# shoulder.net
KiCad netlist of a schematic drawn in EAGLE
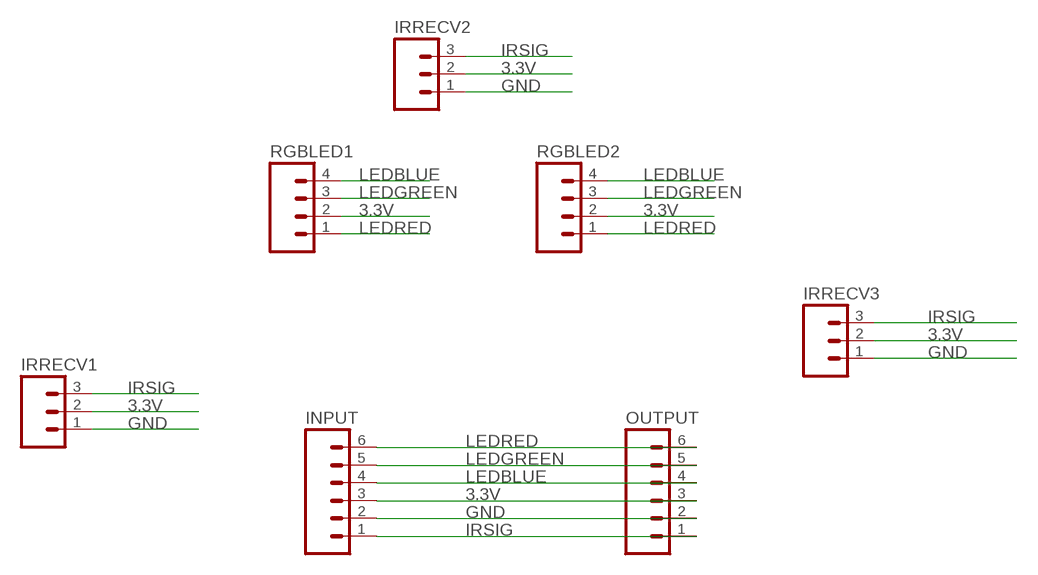
[diagram p0: schematic, sheet 1]

(export (version "E")
  (design (tool "Eeschema 10.0.6"))
  (components
    (comp (ref "INPUT")
      (value "M06SILK_FEMALE_PTH")
      (footprint "eagle-import:1X06")
      (libsource (lib "eagle-import") (part "M06SILK_FEMALE_PTH"))
    )
    (comp (ref "IRRECV1")
      (value "M03PTH")
      (footprint "eagle-import:1X03")
      (libsource (lib "eagle-import") (part "M03PTH"))
    )
    (comp (ref "IRRECV2")
      (value "M03PTH")
      (footprint "eagle-import:1X03")
      (libsource (lib "eagle-import") (part "M03PTH"))
    )
    (comp (ref "IRRECV3")
      (value "M03PTH")
      (footprint "eagle-import:1X03")
      (libsource (lib "eagle-import") (part "M03PTH"))
    )
    (comp (ref "OUTPUT")
      (value "M06SILK_FEMALE_PTH")
      (footprint "eagle-import:1X06")
      (libsource (lib "eagle-import") (part "M06SILK_FEMALE_PTH"))
    )
    (comp (ref "RGBLED1")
      (value "M04PTH")
      (footprint "eagle-import:1X04")
      (libsource (lib "eagle-import") (part "M04PTH"))
    )
    (comp (ref "RGBLED2")
      (value "M04PTH")
      (footprint "eagle-import:1X04")
      (libsource (lib "eagle-import") (part "M04PTH"))
    )
  )
  (nets
    (net (code "1") (name "/3.3V") (class "Default")
      (node (ref "INPUT") (pin "3") (pinfunction "3_3") (pintype "passive"))
      (node (ref "IRRECV1") (pin "2") (pinfunction "2_2") (pintype "passive"))
      (node (ref "IRRECV2") (pin "2") (pinfunction "2_2") (pintype "passive"))
      (node (ref "IRRECV3") (pin "2") (pinfunction "2_2") (pintype "passive"))
      (node (ref "OUTPUT") (pin "3") (pinfunction "3_3") (pintype "passive"))
      (node (ref "RGBLED1") (pin "2") (pinfunction "2_2") (pintype "passive"))
      (node (ref "RGBLED2") (pin "2") (pinfunction "2_2") (pintype "passive"))
    )
    (net (code "2") (name "/GND") (class "Default")
      (node (ref "INPUT") (pin "2") (pinfunction "2_2") (pintype "passive"))
      (node (ref "IRRECV1") (pin "1") (pinfunction "1_1") (pintype "passive"))
      (node (ref "IRRECV2") (pin "1") (pinfunction "1_1") (pintype "passive"))
      (node (ref "IRRECV3") (pin "1") (pinfunction "1_1") (pintype "passive"))
      (node (ref "OUTPUT") (pin "2") (pinfunction "2_2") (pintype "passive"))
    )
    (net (code "3") (name "/IRSIG") (class "Default")
      (node (ref "INPUT") (pin "1") (pinfunction "1_1") (pintype "passive"))
      (node (ref "IRRECV1") (pin "3") (pinfunction "3_3") (pintype "passive"))
      (node (ref "IRRECV2") (pin "3") (pinfunction "3_3") (pintype "passive"))
      (node (ref "IRRECV3") (pin "3") (pinfunction "3_3") (pintype "passive"))
      (node (ref "OUTPUT") (pin "1") (pinfunction "1_1") (pintype "passive"))
    )
    (net (code "4") (name "/LEDBLUE") (class "Default")
      (node (ref "INPUT") (pin "4") (pinfunction "4_4") (pintype "passive"))
      (node (ref "OUTPUT") (pin "4") (pinfunction "4_4") (pintype "passive"))
      (node (ref "RGBLED1") (pin "4") (pinfunction "4_4") (pintype "passive"))
      (node (ref "RGBLED2") (pin "4") (pinfunction "4_4") (pintype "passive"))
    )
    (net (code "5") (name "/LEDGREEN") (class "Default")
      (node (ref "INPUT") (pin "5") (pinfunction "5_5") (pintype "passive"))
      (node (ref "OUTPUT") (pin "5") (pinfunction "5_5") (pintype "passive"))
      (node (ref "RGBLED1") (pin "3") (pinfunction "3_3") (pintype "passive"))
      (node (ref "RGBLED2") (pin "3") (pinfunction "3_3") (pintype "passive"))
    )
    (net (code "6") (name "/LEDRED") (class "Default")
      (node (ref "INPUT") (pin "6") (pinfunction "6_6") (pintype "passive"))
      (node (ref "OUTPUT") (pin "6") (pinfunction "6_6") (pintype "passive"))
      (node (ref "RGBLED1") (pin "1") (pinfunction "1_1") (pintype "passive"))
      (node (ref "RGBLED2") (pin "1") (pinfunction "1_1") (pintype "passive"))
    )
  )
)
